# Rechargeable.net
KiCad netlist of a schematic drawn in EAGLE
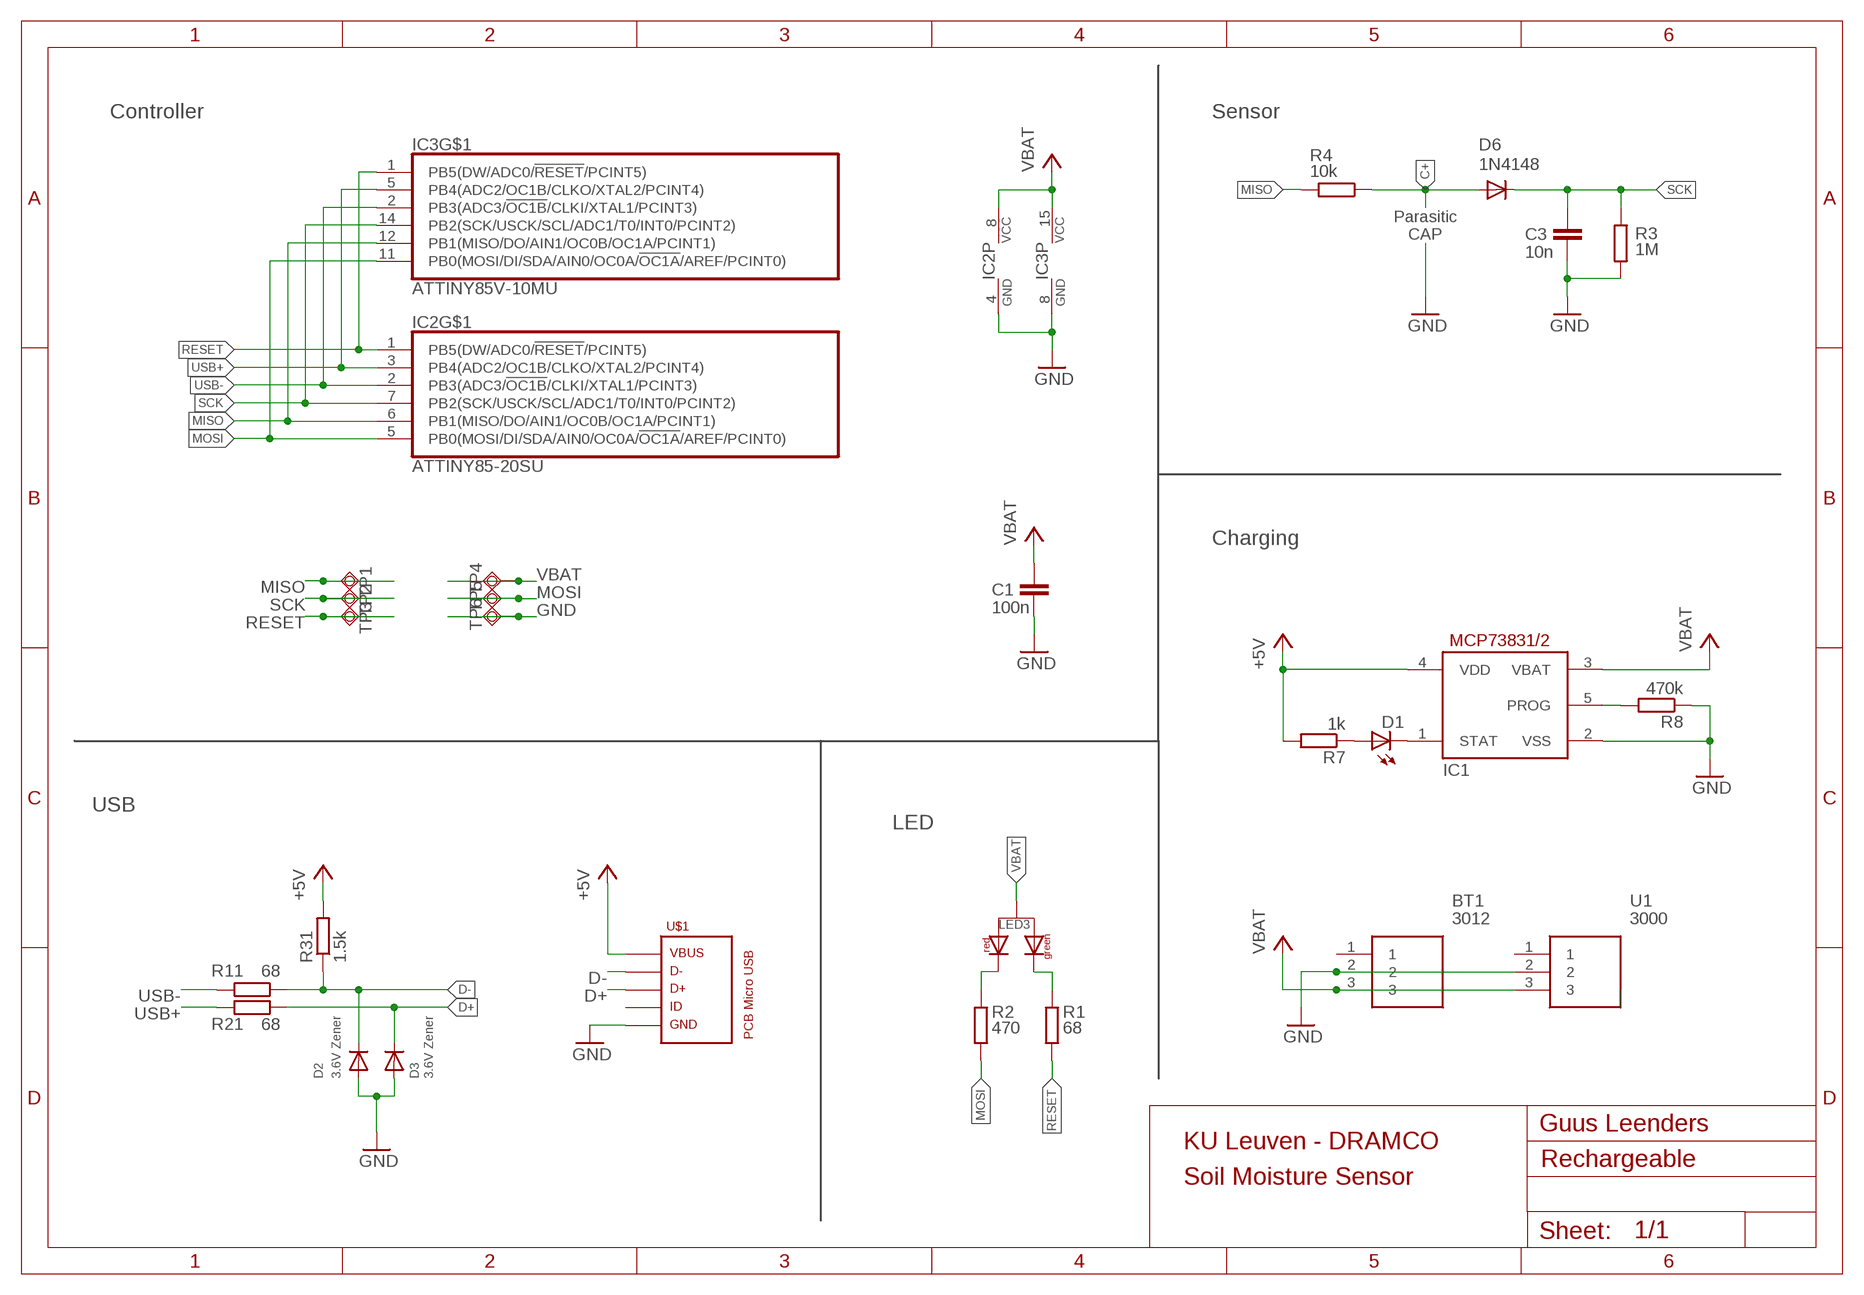
[diagram p0: schematic, sheet 1]

(export (version "E")
  (design (tool "Eeschema 10.0.6"))
  (components
    (comp (ref "BT1")
      (value "3012")
      (footprint "eagle-import:3012")
      (fields (field (name "MOUSER_PART_NUMBER") "534-3012"))
      (libsource (lib "eagle-import") (part "3012"))
    )
    (comp (ref "C1")
      (value "100n")
      (footprint "eagle-import:C0603")
      (libsource (lib "eagle-import") (part "C-EUC0603"))
    )
    (comp (ref "C3")
      (value "10n")
      (footprint "eagle-import:C025-024X044")
      (libsource (lib "eagle-import") (part "resistor_C-EU025-024X044"))
    )
    (comp (ref "D1")
      (value "LEDCHIP-LED0603")
      (footprint "eagle-import:CHIP-LED0603")
      (libsource (lib "eagle-import") (part "LEDCHIP-LED0603"))
    )
    (comp (ref "D2")
      (value "3.6V Zener")
      (footprint "eagle-import:SOD-323F")
      (libsource (lib "eagle-import") (part "DIODESOD-323F"))
    )
    (comp (ref "D3")
      (value "3.6V Zener")
      (footprint "eagle-import:SOD-323F")
      (libsource (lib "eagle-import") (part "DIODESOD-323F"))
    )
    (comp (ref "D6")
      (value "1N4148")
      (footprint "eagle-import:D-5")
      (libsource (lib "eagle-import") (part "DIODE-D-5"))
    )
    (comp (ref "IC1")
      (value "MCP73831/OT")
      (footprint "eagle-import:SOT23-5L")
      (libsource (lib "eagle-import") (part "MCP73831/OT"))
    )
    (comp (ref "IC2")
      (value "ATTINY85-20SU")
      (footprint "eagle-import:8S2")
      (libsource (lib "eagle-import") (part "ATTINY5-20SU8"))
    )
    (comp (ref "IC3")
      (value "ATTINY85V-10MU")
      (footprint "eagle-import:QFN20_4X4_0.50")
      (libsource (lib "eagle-import") (part "ATTINY5V-10MU8"))
    )
    (comp (ref "LED3")
      (value "KPBA-3010SURKCGKC3MM")
      (footprint "eagle-import:3MMLED")
      (libsource (lib "eagle-import") (part "KPBA-3010SURKCGKC3MM"))
    )
    (comp (ref "R1")
      (value "68")
      (footprint "eagle-import:0204_7")
      (libsource (lib "eagle-import") (part "resistor_R-EU_0204/7"))
    )
    (comp (ref "R2")
      (value "470")
      (footprint "eagle-import:0204_7")
      (libsource (lib "eagle-import") (part "resistor_R-EU_0204/7"))
    )
    (comp (ref "R3")
      (value "1M")
      (footprint "eagle-import:0204_7")
      (libsource (lib "eagle-import") (part "resistor_R-EU_0204/7"))
    )
    (comp (ref "R4")
      (value "10k")
      (footprint "eagle-import:0204_7")
      (libsource (lib "eagle-import") (part "resistor_R-EU_0204/7"))
    )
    (comp (ref "R7")
      (value "1k")
      (footprint "eagle-import:R0603")
      (libsource (lib "eagle-import") (part "R-EU_R0603"))
    )
    (comp (ref "R8")
      (value "470k")
      (footprint "eagle-import:R0603")
      (libsource (lib "eagle-import") (part "R-EU_R0603"))
    )
    (comp (ref "R11")
      (value "68")
      (footprint "eagle-import:R0603")
      (libsource (lib "eagle-import") (part "R-EU_R0603"))
    )
    (comp (ref "R21")
      (value "68")
      (footprint "eagle-import:R0603")
      (libsource (lib "eagle-import") (part "R-EU_R0603"))
    )
    (comp (ref "R31")
      (value "1.5k")
      (footprint "eagle-import:R0603")
      (libsource (lib "eagle-import") (part "R-EU_R0603"))
    )
    (comp (ref "TP1")
      (value "TPSQTP15R")
      (footprint "eagle-import:TP15R")
      (libsource (lib "eagle-import") (part "TPSQTP15R"))
    )
    (comp (ref "TP2")
      (value "TPSQTP15R")
      (footprint "eagle-import:TP15R")
      (libsource (lib "eagle-import") (part "TPSQTP15R"))
    )
    (comp (ref "TP3")
      (value "TPSQTP15R")
      (footprint "eagle-import:TP15R")
      (libsource (lib "eagle-import") (part "TPSQTP15R"))
    )
    (comp (ref "TP4")
      (value "TPSQTP15R")
      (footprint "eagle-import:TP15R")
      (libsource (lib "eagle-import") (part "TPSQTP15R"))
    )
    (comp (ref "TP5")
      (value "TPSQTP15R")
      (footprint "eagle-import:TP15R")
      (libsource (lib "eagle-import") (part "TPSQTP15R"))
    )
    (comp (ref "TP6")
      (value "TPSQTP15SQ")
      (footprint "eagle-import:TP15SQ")
      (libsource (lib "eagle-import") (part "TPSQTP15SQ"))
    )
    (comp (ref "U$1")
      (value "PCB_MICRO_USB_BSS_3")
      (footprint "eagle-import:USB_TYPE_B_SS_3")
      (libsource (lib "eagle-import") (part "PCB_MICRO_USB_BSS_3"))
    )
    (comp (ref "U1")
      (value "3000")
      (footprint "eagle-import:3000")
      (fields (field (name "MOUSER_PART_NUMBER") "534-3000"))
      (libsource (lib "eagle-import") (part "3000"))
    )
  )
  (nets
    (net (code "1") (name "+5V") (class "Default")
      (node (ref "IC1") (pin "4") (pinfunction "VDD_4") (pintype "power_in"))
      (node (ref "R31") (pin "2") (pinfunction "2_2") (pintype "passive"))
      (node (ref "R7") (pin "2") (pinfunction "2_2") (pintype "passive"))
      (node (ref "U$1") (pin "1") (pinfunction "1_1") (pintype "bidirectional"))
    )
    (net (code "2") (name "C+") (class "Default")
      (node (ref "D6") (pin "A") (pinfunction "A_A") (pintype "passive"))
      (node (ref "R4") (pin "1") (pinfunction "1_1") (pintype "passive"))
    )
    (net (code "3") (name "D+") (class "Default")
      (node (ref "D3") (pin "C") (pinfunction "C_C") (pintype "passive"))
      (node (ref "R21") (pin "1") (pinfunction "1_1") (pintype "passive"))
      (node (ref "U$1") (pin "3") (pinfunction "3_3") (pintype "bidirectional"))
    )
    (net (code "4") (name "D-") (class "Default")
      (node (ref "D2") (pin "C") (pinfunction "C_C") (pintype "passive"))
      (node (ref "R11") (pin "1") (pinfunction "1_1") (pintype "passive"))
      (node (ref "R31") (pin "1") (pinfunction "1_1") (pintype "passive"))
      (node (ref "U$1") (pin "2") (pinfunction "2_2") (pintype "bidirectional"))
    )
    (net (code "5") (name "GND") (class "Default")
      (node (ref "BT1") (pin "2") (pinfunction "2_2") (pintype "bidirectional"))
      (node (ref "C1") (pin "2") (pinfunction "2_2") (pintype "passive"))
      (node (ref "C3") (pin "2") (pinfunction "2_2") (pintype "passive"))
      (node (ref "D2") (pin "A") (pinfunction "A_A") (pintype "passive"))
      (node (ref "D3") (pin "A") (pinfunction "A_A") (pintype "passive"))
      (node (ref "IC1") (pin "2") (pinfunction "VSS_2") (pintype "power_in"))
      (node (ref "IC2") (pin "4") (pinfunction "GND_4") (pintype "power_in"))
      (node (ref "IC3") (pin "8") (pinfunction "GND_8") (pintype "power_in"))
      (node (ref "R3") (pin "2") (pinfunction "2_2") (pintype "passive"))
      (node (ref "R8") (pin "1") (pinfunction "1_1") (pintype "passive"))
      (node (ref "TP6") (pin "TP") (pinfunction "TP_TP") (pintype "input"))
      (node (ref "U$1") (pin "5") (pinfunction "5_5") (pintype "bidirectional"))
      (node (ref "U1") (pin "2") (pinfunction "2_2") (pintype "bidirectional"))
    )
    (net (code "6") (name "MISO") (class "Default")
      (node (ref "IC2") (pin "6") (pinfunction "PB1(MISO/DO/AIN1/OC0B/OC1A/PCINT1)_6") (pintype "bidirectional"))
      (node (ref "IC3") (pin "12") (pinfunction "PB1(MISO/DO/AIN1/OC0B/OC1A/PCINT1)_12") (pintype "bidirectional"))
      (node (ref "R4") (pin "2") (pinfunction "2_2") (pintype "passive"))
      (node (ref "TP1") (pin "TP") (pinfunction "TP_TP") (pintype "input"))
    )
    (net (code "7") (name "MOSI") (class "Default")
      (node (ref "IC2") (pin "5") (pinfunction "PB0(MOSI/DI/SDA/AIN0/OC0A/~{OC1A}/AREF/PCINT0)_5") (pintype "bidirectional"))
      (node (ref "IC3") (pin "11") (pinfunction "PB0(MOSI/DI/SDA/AIN0/OC0A/~{OC1A}/AREF/PCINT0)_11") (pintype "bidirectional"))
      (node (ref "R2") (pin "2") (pinfunction "2_2") (pintype "passive"))
      (node (ref "TP5") (pin "TP") (pinfunction "TP_TP") (pintype "input"))
    )
    (net (code "8") (name "Net-(D1-PadA)") (class "Default")
      (node (ref "D1") (pin "A") (pinfunction "A_A") (pintype "passive"))
      (node (ref "R7") (pin "1") (pinfunction "1_1") (pintype "passive"))
    )
    (net (code "9") (name "Net-(IC1-PROG)") (class "Default")
      (node (ref "IC1") (pin "5") (pinfunction "PROG_5") (pintype "input"))
      (node (ref "R8") (pin "2") (pinfunction "2_2") (pintype "passive"))
    )
    (net (code "10") (name "Net-(IC1-STAT)") (class "Default")
      (node (ref "D1") (pin "C") (pinfunction "C_C") (pintype "passive"))
      (node (ref "IC1") (pin "1") (pinfunction "STAT_1") (pintype "output"))
    )
    (net (code "11") (name "Net-(LED3-P$2)") (class "Default")
      (node (ref "LED3") (pin "-1") (pinfunction "P$2_-1") (pintype "passive"))
      (node (ref "R2") (pin "1") (pinfunction "1_1") (pintype "passive"))
    )
    (net (code "12") (name "Net-(LED3-P$3)") (class "Default")
      (node (ref "LED3") (pin "-2") (pinfunction "P$3_-2") (pintype "passive"))
      (node (ref "R1") (pin "1") (pinfunction "1_1") (pintype "passive"))
    )
    (net (code "13") (name "RESET") (class "Default")
      (node (ref "IC2") (pin "1") (pinfunction "PB5(DW/ADC0/~{RESET}/PCINT5)_1") (pintype "bidirectional"))
      (node (ref "IC3") (pin "1") (pinfunction "PB5(DW/ADC0/~{RESET}/PCINT5)_1") (pintype "bidirectional"))
      (node (ref "R1") (pin "2") (pinfunction "2_2") (pintype "passive"))
      (node (ref "TP3") (pin "TP") (pinfunction "TP_TP") (pintype "input"))
    )
    (net (code "14") (name "SCK") (class "Default")
      (node (ref "C3") (pin "1") (pinfunction "1_1") (pintype "passive"))
      (node (ref "D6") (pin "C") (pinfunction "C_C") (pintype "passive"))
      (node (ref "IC2") (pin "7") (pinfunction "PB2(SCK/USCK/SCL/ADC1/T0/INT0/PCINT2)_7") (pintype "bidirectional"))
      (node (ref "IC3") (pin "14") (pinfunction "PB2(SCK/USCK/SCL/ADC1/T0/INT0/PCINT2)_14") (pintype "bidirectional"))
      (node (ref "R3") (pin "1") (pinfunction "1_1") (pintype "passive"))
      (node (ref "TP2") (pin "TP") (pinfunction "TP_TP") (pintype "input"))
    )
    (net (code "15") (name "USB+") (class "Default")
      (node (ref "IC2") (pin "3") (pinfunction "PB4(ADC2/OC1B/CLKO/XTAL2/PCINT4)_3") (pintype "bidirectional"))
      (node (ref "IC3") (pin "5") (pinfunction "PB4(ADC2/OC1B/CLKO/XTAL2/PCINT4)_5") (pintype "bidirectional"))
      (node (ref "R21") (pin "2") (pinfunction "2_2") (pintype "passive"))
    )
    (net (code "16") (name "USB-") (class "Default")
      (node (ref "IC2") (pin "2") (pinfunction "PB3(ADC3/~{OC1B}/CLKI/XTAL1/PCINT3)_2") (pintype "bidirectional"))
      (node (ref "IC3") (pin "2") (pinfunction "PB3(ADC3/~{OC1B}/CLKI/XTAL1/PCINT3)_2") (pintype "bidirectional"))
      (node (ref "R11") (pin "2") (pinfunction "2_2") (pintype "passive"))
    )
    (net (code "17") (name "VBAT") (class "Default")
      (node (ref "BT1") (pin "3") (pinfunction "3_3") (pintype "bidirectional"))
      (node (ref "C1") (pin "1") (pinfunction "1_1") (pintype "passive"))
      (node (ref "IC1") (pin "3") (pinfunction "VBAT_3") (pintype "bidirectional"))
      (node (ref "IC2") (pin "8") (pinfunction "VCC_8") (pintype "power_in"))
      (node (ref "IC3") (pin "15") (pinfunction "VCC_15") (pintype "power_in"))
      (node (ref "LED3") (pin "+") (pinfunction "P$1_+") (pintype "passive"))
      (node (ref "TP4") (pin "TP") (pinfunction "TP_TP") (pintype "input"))
      (node (ref "U1") (pin "3") (pinfunction "3_3") (pintype "bidirectional"))
    )
    (net (code "18") (name "unconnected-(BT1-Pad1)") (class "Default")
      (node (ref "BT1") (pin "1") (pinfunction "1_1") (pintype "bidirectional"))
    )
    (net (code "19") (name "unconnected-(U$1-Pad4)") (class "Default")
      (node (ref "U$1") (pin "4") (pinfunction "4_4") (pintype "bidirectional"))
    )
    (net (code "20") (name "unconnected-(U1-Pad1)") (class "Default")
      (node (ref "U1") (pin "1") (pinfunction "1_1") (pintype "bidirectional"))
    )
  )
)
